# PCB-BI16-466.net
KiCad netlist of a schematic drawn in EAGLE
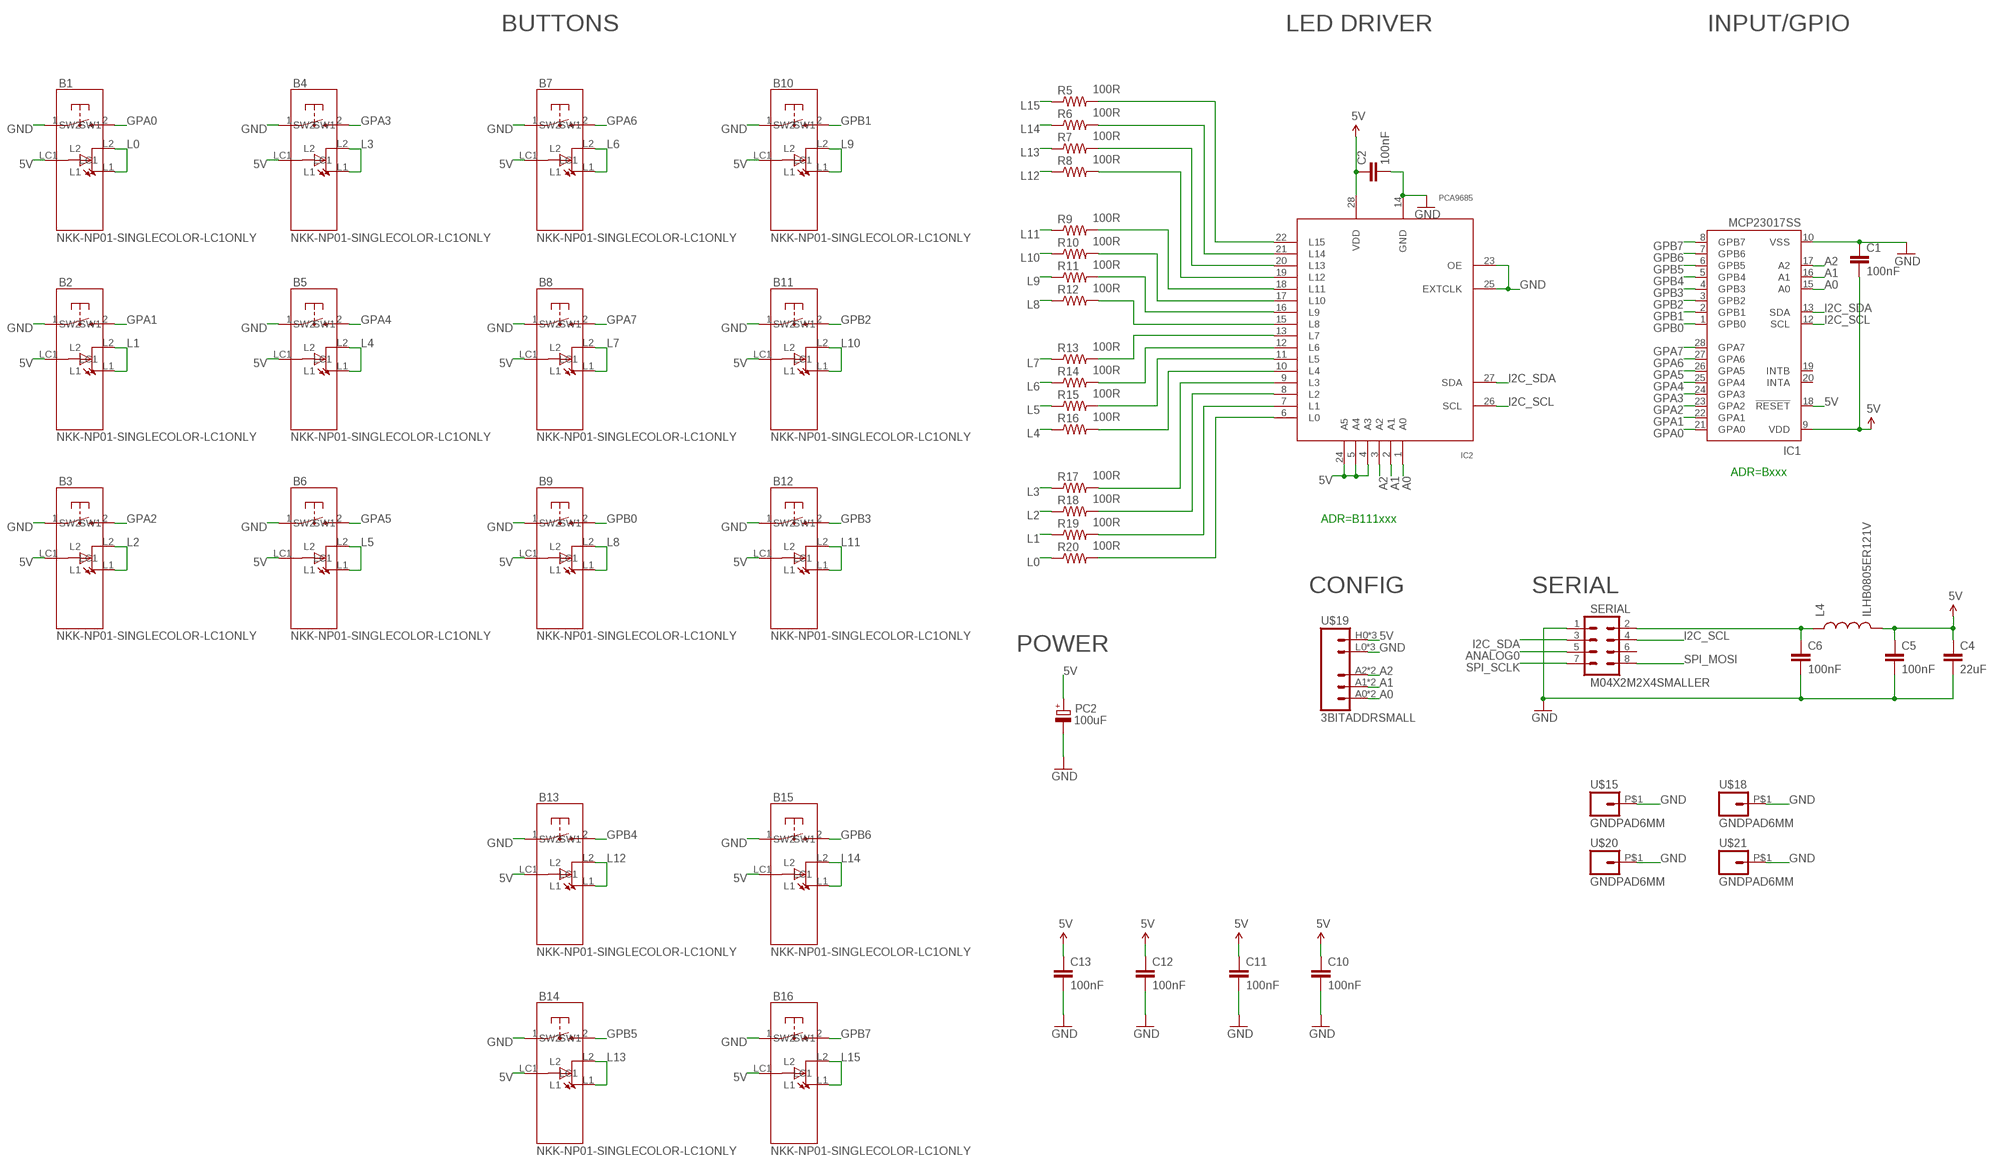
[diagram p0: schematic, sheet 1]

(export (version "E")
  (design (tool "Eeschema 10.0.6"))
  (components
    (comp (ref "B1")
      (value "NKK-NP01-SINGLECOLOR-LC1ONLY")
      (footprint "eagle-import:NKK-NP01_LESSHOLES2")
      (libsource (lib "eagle-import") (part "NKK-NP01-SINGLECOLOR-LC1ONLY"))
    )
    (comp (ref "B2")
      (value "NKK-NP01-SINGLECOLOR-LC1ONLY")
      (footprint "eagle-import:NKK-NP01_LESSHOLES2")
      (libsource (lib "eagle-import") (part "NKK-NP01-SINGLECOLOR-LC1ONLY"))
    )
    (comp (ref "B3")
      (value "NKK-NP01-SINGLECOLOR-LC1ONLY")
      (footprint "eagle-import:NKK-NP01_LESSHOLES2")
      (libsource (lib "eagle-import") (part "NKK-NP01-SINGLECOLOR-LC1ONLY"))
    )
    (comp (ref "B4")
      (value "NKK-NP01-SINGLECOLOR-LC1ONLY")
      (footprint "eagle-import:NKK-NP01_LESSHOLES2")
      (libsource (lib "eagle-import") (part "NKK-NP01-SINGLECOLOR-LC1ONLY"))
    )
    (comp (ref "B5")
      (value "NKK-NP01-SINGLECOLOR-LC1ONLY")
      (footprint "eagle-import:NKK-NP01_LESSHOLES2")
      (libsource (lib "eagle-import") (part "NKK-NP01-SINGLECOLOR-LC1ONLY"))
    )
    (comp (ref "B6")
      (value "NKK-NP01-SINGLECOLOR-LC1ONLY")
      (footprint "eagle-import:NKK-NP01_LESSHOLES2")
      (libsource (lib "eagle-import") (part "NKK-NP01-SINGLECOLOR-LC1ONLY"))
    )
    (comp (ref "B7")
      (value "NKK-NP01-SINGLECOLOR-LC1ONLY")
      (footprint "eagle-import:NKK-NP01_LESSHOLES2")
      (libsource (lib "eagle-import") (part "NKK-NP01-SINGLECOLOR-LC1ONLY"))
    )
    (comp (ref "B8")
      (value "NKK-NP01-SINGLECOLOR-LC1ONLY")
      (footprint "eagle-import:NKK-NP01_LESSHOLES2")
      (libsource (lib "eagle-import") (part "NKK-NP01-SINGLECOLOR-LC1ONLY"))
    )
    (comp (ref "B9")
      (value "NKK-NP01-SINGLECOLOR-LC1ONLY")
      (footprint "eagle-import:NKK-NP01_LESSHOLES2")
      (libsource (lib "eagle-import") (part "NKK-NP01-SINGLECOLOR-LC1ONLY"))
    )
    (comp (ref "B10")
      (value "NKK-NP01-SINGLECOLOR-LC1ONLY")
      (footprint "eagle-import:NKK-NP01_LESSHOLES2")
      (libsource (lib "eagle-import") (part "NKK-NP01-SINGLECOLOR-LC1ONLY"))
    )
    (comp (ref "B11")
      (value "NKK-NP01-SINGLECOLOR-LC1ONLY")
      (footprint "eagle-import:NKK-NP01_LESSHOLES2")
      (libsource (lib "eagle-import") (part "NKK-NP01-SINGLECOLOR-LC1ONLY"))
    )
    (comp (ref "B12")
      (value "NKK-NP01-SINGLECOLOR-LC1ONLY")
      (footprint "eagle-import:NKK-NP01_LESSHOLES2")
      (libsource (lib "eagle-import") (part "NKK-NP01-SINGLECOLOR-LC1ONLY"))
    )
    (comp (ref "B13")
      (value "NKK-NP01-SINGLECOLOR-LC1ONLY")
      (footprint "eagle-import:NKK-NP01_LESSHOLES2")
      (libsource (lib "eagle-import") (part "NKK-NP01-SINGLECOLOR-LC1ONLY"))
    )
    (comp (ref "B14")
      (value "NKK-NP01-SINGLECOLOR-LC1ONLY")
      (footprint "eagle-import:NKK-NP01_LESSHOLES2")
      (libsource (lib "eagle-import") (part "NKK-NP01-SINGLECOLOR-LC1ONLY"))
    )
    (comp (ref "B15")
      (value "NKK-NP01-SINGLECOLOR-LC1ONLY")
      (footprint "eagle-import:NKK-NP01_LESSHOLES2")
      (libsource (lib "eagle-import") (part "NKK-NP01-SINGLECOLOR-LC1ONLY"))
    )
    (comp (ref "B16")
      (value "NKK-NP01-SINGLECOLOR-LC1ONLY")
      (footprint "eagle-import:NKK-NP01_LESSHOLES2")
      (libsource (lib "eagle-import") (part "NKK-NP01-SINGLECOLOR-LC1ONLY"))
    )
    (comp (ref "C1")
      (value "100nF")
      (footprint "eagle-import:0603-CAP")
      (libsource (lib "eagle-import") (part "CAP0603-CAP"))
    )
    (comp (ref "C2")
      (value "100nF")
      (footprint "eagle-import:0603-CAP")
      (libsource (lib "eagle-import") (part "CAP0603-CAP"))
    )
    (comp (ref "C4")
      (value "22uF")
      (footprint "eagle-import:0805")
      (libsource (lib "eagle-import") (part "CAP0805"))
    )
    (comp (ref "C5")
      (value "100nF")
      (footprint "eagle-import:0603-CAP")
      (libsource (lib "eagle-import") (part "CAP0603-CAP"))
    )
    (comp (ref "C6")
      (value "100nF")
      (footprint "eagle-import:0603-CAP")
      (libsource (lib "eagle-import") (part "CAP0603-CAP"))
    )
    (comp (ref "C10")
      (value "100nF")
      (footprint "eagle-import:0603-CAP")
      (libsource (lib "eagle-import") (part "CAP0603-CAP"))
    )
    (comp (ref "C11")
      (value "100nF")
      (footprint "eagle-import:0603-CAP")
      (libsource (lib "eagle-import") (part "CAP0603-CAP"))
    )
    (comp (ref "C12")
      (value "100nF")
      (footprint "eagle-import:0603-CAP")
      (libsource (lib "eagle-import") (part "CAP0603-CAP"))
    )
    (comp (ref "C13")
      (value "100nF")
      (footprint "eagle-import:0603-CAP")
      (libsource (lib "eagle-import") (part "CAP0603-CAP"))
    )
    (comp (ref "IC1")
      (value "MCP23017SS")
      (footprint "eagle-import:SSOP28")
      (fields
        (field (name "MF") "MICROCHIP")
        (field (name "MPN") "MCP23017-E/SS")
        (field (name "MPN_1") "MCP23017-E/SS")
        (field (name "OC_FARNELL") "1467674")
        (field (name "OC_NEWARK") "31K2960")
      )
      (libsource (lib "eagle-import") (part "MCP23017SS"))
    )
    (comp (ref "IC2")
      (value "PCA9685")
      (footprint "eagle-import:TSSOP28")
      (libsource (lib "eagle-import") (part "PCA9685"))
    )
    (comp (ref "L4")
      (value "ILHB0805ER121V")
      (footprint "eagle-import:0805")
      (libsource (lib "eagle-import") (part "INDUCTOR0805"))
    )
    (comp (ref "PC2")
      (value "100uF")
      (footprint "eagle-import:PANASONIC_D")
      (libsource (lib "eagle-import") (part "CPOL-EUD"))
    )
    (comp (ref "R5")
      (value "100R")
      (footprint "eagle-import:0603-RES")
      (libsource (lib "eagle-import") (part "RESISTOR0603-RES"))
    )
    (comp (ref "R6")
      (value "100R")
      (footprint "eagle-import:0603-RES")
      (libsource (lib "eagle-import") (part "RESISTOR0603-RES"))
    )
    (comp (ref "R7")
      (value "100R")
      (footprint "eagle-import:0603-RES")
      (libsource (lib "eagle-import") (part "RESISTOR0603-RES"))
    )
    (comp (ref "R8")
      (value "100R")
      (footprint "eagle-import:0603-RES")
      (libsource (lib "eagle-import") (part "RESISTOR0603-RES"))
    )
    (comp (ref "R9")
      (value "100R")
      (footprint "eagle-import:0603-RES")
      (libsource (lib "eagle-import") (part "RESISTOR0603-RES"))
    )
    (comp (ref "R10")
      (value "100R")
      (footprint "eagle-import:0603-RES")
      (libsource (lib "eagle-import") (part "RESISTOR0603-RES"))
    )
    (comp (ref "R11")
      (value "100R")
      (footprint "eagle-import:0603-RES")
      (libsource (lib "eagle-import") (part "RESISTOR0603-RES"))
    )
    (comp (ref "R12")
      (value "100R")
      (footprint "eagle-import:0603-RES")
      (libsource (lib "eagle-import") (part "RESISTOR0603-RES"))
    )
    (comp (ref "R13")
      (value "100R")
      (footprint "eagle-import:0603-RES")
      (libsource (lib "eagle-import") (part "RESISTOR0603-RES"))
    )
    (comp (ref "R14")
      (value "100R")
      (footprint "eagle-import:0603-RES")
      (libsource (lib "eagle-import") (part "RESISTOR0603-RES"))
    )
    (comp (ref "R15")
      (value "100R")
      (footprint "eagle-import:0603-RES")
      (libsource (lib "eagle-import") (part "RESISTOR0603-RES"))
    )
    (comp (ref "R16")
      (value "100R")
      (footprint "eagle-import:0603-RES")
      (libsource (lib "eagle-import") (part "RESISTOR0603-RES"))
    )
    (comp (ref "R17")
      (value "100R")
      (footprint "eagle-import:0603-RES")
      (libsource (lib "eagle-import") (part "RESISTOR0603-RES"))
    )
    (comp (ref "R18")
      (value "100R")
      (footprint "eagle-import:0603-RES")
      (libsource (lib "eagle-import") (part "RESISTOR0603-RES"))
    )
    (comp (ref "R19")
      (value "100R")
      (footprint "eagle-import:0603-RES")
      (libsource (lib "eagle-import") (part "RESISTOR0603-RES"))
    )
    (comp (ref "R20")
      (value "100R")
      (footprint "eagle-import:0603-RES")
      (libsource (lib "eagle-import") (part "RESISTOR0603-RES"))
    )
    (comp (ref "SERIAL")
      (value "M04X2M2X4SMALLER")
      (footprint "eagle-import:M2X4SMALLER")
      (libsource (lib "eagle-import") (part "M04X2M2X4SMALLER"))
    )
    (comp (ref "U$15")
      (value "GNDPAD6MM")
      (footprint "eagle-import:3.2MMPAD6MM")
      (libsource (lib "eagle-import") (part "GNDPAD6MM"))
    )
    (comp (ref "U$18")
      (value "GNDPAD6MM")
      (footprint "eagle-import:3.2MMPAD6MM")
      (libsource (lib "eagle-import") (part "GNDPAD6MM"))
    )
    (comp (ref "U$19")
      (value "3BITADDRSMALL")
      (footprint "eagle-import:3BITADDR_SMALL")
      (libsource (lib "eagle-import") (part "3BITADDRSMALL"))
    )
    (comp (ref "U$20")
      (value "GNDPAD6MM")
      (footprint "eagle-import:3.2MMPAD6MM")
      (libsource (lib "eagle-import") (part "GNDPAD6MM"))
    )
    (comp (ref "U$21")
      (value "GNDPAD6MM")
      (footprint "eagle-import:3.2MMPAD6MM")
      (libsource (lib "eagle-import") (part "GNDPAD6MM"))
    )
  )
  (nets
    (net (code "1") (name "5V") (class "Default")
      (node (ref "B1") (pin "LC1") (pinfunction "LC1_LC1") (pintype "bidirectional"))
      (node (ref "B10") (pin "LC1") (pinfunction "LC1_LC1") (pintype "bidirectional"))
      (node (ref "B11") (pin "LC1") (pinfunction "LC1_LC1") (pintype "bidirectional"))
      (node (ref "B12") (pin "LC1") (pinfunction "LC1_LC1") (pintype "bidirectional"))
      (node (ref "B13") (pin "LC1") (pinfunction "LC1_LC1") (pintype "bidirectional"))
      (node (ref "B14") (pin "LC1") (pinfunction "LC1_LC1") (pintype "bidirectional"))
      (node (ref "B15") (pin "LC1") (pinfunction "LC1_LC1") (pintype "bidirectional"))
      (node (ref "B16") (pin "LC1") (pinfunction "LC1_LC1") (pintype "bidirectional"))
      (node (ref "B2") (pin "LC1") (pinfunction "LC1_LC1") (pintype "bidirectional"))
      (node (ref "B3") (pin "LC1") (pinfunction "LC1_LC1") (pintype "bidirectional"))
      (node (ref "B4") (pin "LC1") (pinfunction "LC1_LC1") (pintype "bidirectional"))
      (node (ref "B5") (pin "LC1") (pinfunction "LC1_LC1") (pintype "bidirectional"))
      (node (ref "B6") (pin "LC1") (pinfunction "LC1_LC1") (pintype "bidirectional"))
      (node (ref "B7") (pin "LC1") (pinfunction "LC1_LC1") (pintype "bidirectional"))
      (node (ref "B8") (pin "LC1") (pinfunction "LC1_LC1") (pintype "bidirectional"))
      (node (ref "B9") (pin "LC1") (pinfunction "LC1_LC1") (pintype "bidirectional"))
      (node (ref "C1") (pin "2") (pinfunction "2_2") (pintype "passive"))
      (node (ref "C10") (pin "1") (pinfunction "1_1") (pintype "passive"))
      (node (ref "C11") (pin "1") (pinfunction "1_1") (pintype "passive"))
      (node (ref "C12") (pin "1") (pinfunction "1_1") (pintype "passive"))
      (node (ref "C13") (pin "1") (pinfunction "1_1") (pintype "passive"))
      (node (ref "C2") (pin "1") (pinfunction "1_1") (pintype "passive"))
      (node (ref "C4") (pin "1") (pinfunction "1_1") (pintype "passive"))
      (node (ref "C5") (pin "1") (pinfunction "1_1") (pintype "passive"))
      (node (ref "IC1") (pin "18") (pinfunction "~{RESET}_18") (pintype "input"))
      (node (ref "IC1") (pin "9") (pinfunction "VDD_9") (pintype "power_in"))
      (node (ref "IC2") (pin "24") (pinfunction "A5_24") (pintype "input"))
      (node (ref "IC2") (pin "28") (pinfunction "VDD_28") (pintype "power_in"))
      (node (ref "IC2") (pin "4") (pinfunction "A3_4") (pintype "input"))
      (node (ref "IC2") (pin "5") (pinfunction "A4_5") (pintype "input"))
      (node (ref "L4") (pin "2") (pinfunction "2_2") (pintype "passive"))
      (node (ref "PC2") (pin "+") (pinfunction "+_+") (pintype "passive"))
      (node (ref "U$19") (pin "H0") (pinfunction "VCC_H0") (pintype "passive"))
      (node (ref "U$19") (pin "H1") (pinfunction "VCC_H1") (pintype "passive"))
      (node (ref "U$19") (pin "H2") (pinfunction "VCC_H2") (pintype "passive"))
    )
    (net (code "2") (name "A0") (class "Default")
      (node (ref "IC1") (pin "15") (pinfunction "A0_15") (pintype "input"))
      (node (ref "IC2") (pin "1") (pinfunction "A0_1") (pintype "input"))
      (node (ref "U$19") (pin "A0") (pinfunction "A0_A0") (pintype "passive"))
      (node (ref "U$19") (pin "AS0") (pinfunction "A0_AS0") (pintype "passive"))
    )
    (net (code "3") (name "A1") (class "Default")
      (node (ref "IC1") (pin "16") (pinfunction "A1_16") (pintype "input"))
      (node (ref "IC2") (pin "2") (pinfunction "A1_2") (pintype "input"))
      (node (ref "U$19") (pin "A1") (pinfunction "A1_A1") (pintype "passive"))
      (node (ref "U$19") (pin "AS1") (pinfunction "A1_AS1") (pintype "passive"))
    )
    (net (code "4") (name "A2") (class "Default")
      (node (ref "IC1") (pin "17") (pinfunction "A2_17") (pintype "input"))
      (node (ref "IC2") (pin "3") (pinfunction "A2_3") (pintype "input"))
      (node (ref "U$19") (pin "A2") (pinfunction "A2_A2") (pintype "passive"))
      (node (ref "U$19") (pin "AS2") (pinfunction "A2_AS2") (pintype "passive"))
    )
    (net (code "5") (name "ANALOG0") (class "Default")
      (node (ref "SERIAL") (pin "5") (pinfunction "5_5") (pintype "passive"))
    )
    (net (code "6") (name "GND") (class "Default")
      (node (ref "B1") (pin "1") (pinfunction "SW1_1") (pintype "bidirectional"))
      (node (ref "B10") (pin "1") (pinfunction "SW1_1") (pintype "bidirectional"))
      (node (ref "B11") (pin "1") (pinfunction "SW1_1") (pintype "bidirectional"))
      (node (ref "B12") (pin "1") (pinfunction "SW1_1") (pintype "bidirectional"))
      (node (ref "B13") (pin "1") (pinfunction "SW1_1") (pintype "bidirectional"))
      (node (ref "B14") (pin "1") (pinfunction "SW1_1") (pintype "bidirectional"))
      (node (ref "B15") (pin "1") (pinfunction "SW1_1") (pintype "bidirectional"))
      (node (ref "B16") (pin "1") (pinfunction "SW1_1") (pintype "bidirectional"))
      (node (ref "B2") (pin "1") (pinfunction "SW1_1") (pintype "bidirectional"))
      (node (ref "B3") (pin "1") (pinfunction "SW1_1") (pintype "bidirectional"))
      (node (ref "B4") (pin "1") (pinfunction "SW1_1") (pintype "bidirectional"))
      (node (ref "B5") (pin "1") (pinfunction "SW1_1") (pintype "bidirectional"))
      (node (ref "B6") (pin "1") (pinfunction "SW1_1") (pintype "bidirectional"))
      (node (ref "B7") (pin "1") (pinfunction "SW1_1") (pintype "bidirectional"))
      (node (ref "B8") (pin "1") (pinfunction "SW1_1") (pintype "bidirectional"))
      (node (ref "B9") (pin "1") (pinfunction "SW1_1") (pintype "bidirectional"))
      (node (ref "C1") (pin "1") (pinfunction "1_1") (pintype "passive"))
      (node (ref "C10") (pin "2") (pinfunction "2_2") (pintype "passive"))
      (node (ref "C11") (pin "2") (pinfunction "2_2") (pintype "passive"))
      (node (ref "C12") (pin "2") (pinfunction "2_2") (pintype "passive"))
      (node (ref "C13") (pin "2") (pinfunction "2_2") (pintype "passive"))
      (node (ref "C2") (pin "2") (pinfunction "2_2") (pintype "passive"))
      (node (ref "C4") (pin "2") (pinfunction "2_2") (pintype "passive"))
      (node (ref "C5") (pin "2") (pinfunction "2_2") (pintype "passive"))
      (node (ref "C6") (pin "2") (pinfunction "2_2") (pintype "passive"))
      (node (ref "IC1") (pin "10") (pinfunction "VSS_10") (pintype "power_in"))
      (node (ref "IC2") (pin "14") (pinfunction "GND_14") (pintype "power_in"))
      (node (ref "IC2") (pin "23") (pinfunction "OE_23") (pintype "input"))
      (node (ref "IC2") (pin "25") (pinfunction "EXTCLK_25") (pintype "input"))
      (node (ref "PC2") (pin "-") (pinfunction "-_-") (pintype "passive"))
      (node (ref "SERIAL") (pin "1") (pinfunction "1_1") (pintype "passive"))
      (node (ref "U$15") (pin "P$1") (pinfunction "1_P$1") (pintype "passive"))
      (node (ref "U$18") (pin "P$1") (pinfunction "1_P$1") (pintype "passive"))
      (node (ref "U$19") (pin "L0") (pinfunction "GND_L0") (pintype "passive"))
      (node (ref "U$19") (pin "L1") (pinfunction "GND_L1") (pintype "passive"))
      (node (ref "U$19") (pin "L2") (pinfunction "GND_L2") (pintype "passive"))
      (node (ref "U$20") (pin "P$1") (pinfunction "1_P$1") (pintype "passive"))
      (node (ref "U$21") (pin "P$1") (pinfunction "1_P$1") (pintype "passive"))
    )
    (net (code "7") (name "GPA0") (class "Default")
      (node (ref "B1") (pin "2") (pinfunction "SW2_2") (pintype "bidirectional"))
      (node (ref "IC1") (pin "21") (pinfunction "GPA0_21") (pintype "bidirectional"))
    )
    (net (code "8") (name "GPA1") (class "Default")
      (node (ref "B2") (pin "2") (pinfunction "SW2_2") (pintype "bidirectional"))
      (node (ref "IC1") (pin "22") (pinfunction "GPA1_22") (pintype "bidirectional"))
    )
    (net (code "9") (name "GPA2") (class "Default")
      (node (ref "B3") (pin "2") (pinfunction "SW2_2") (pintype "bidirectional"))
      (node (ref "IC1") (pin "23") (pinfunction "GPA2_23") (pintype "bidirectional"))
    )
    (net (code "10") (name "GPA3") (class "Default")
      (node (ref "B4") (pin "2") (pinfunction "SW2_2") (pintype "bidirectional"))
      (node (ref "IC1") (pin "24") (pinfunction "GPA3_24") (pintype "bidirectional"))
    )
    (net (code "11") (name "GPA4") (class "Default")
      (node (ref "B5") (pin "2") (pinfunction "SW2_2") (pintype "bidirectional"))
      (node (ref "IC1") (pin "25") (pinfunction "GPA4_25") (pintype "bidirectional"))
    )
    (net (code "12") (name "GPA5") (class "Default")
      (node (ref "B6") (pin "2") (pinfunction "SW2_2") (pintype "bidirectional"))
      (node (ref "IC1") (pin "26") (pinfunction "GPA5_26") (pintype "bidirectional"))
    )
    (net (code "13") (name "GPA6") (class "Default")
      (node (ref "B7") (pin "2") (pinfunction "SW2_2") (pintype "bidirectional"))
      (node (ref "IC1") (pin "27") (pinfunction "GPA6_27") (pintype "bidirectional"))
    )
    (net (code "14") (name "GPA7") (class "Default")
      (node (ref "B8") (pin "2") (pinfunction "SW2_2") (pintype "bidirectional"))
      (node (ref "IC1") (pin "28") (pinfunction "GPA7_28") (pintype "bidirectional"))
    )
    (net (code "15") (name "GPB0") (class "Default")
      (node (ref "B9") (pin "2") (pinfunction "SW2_2") (pintype "bidirectional"))
      (node (ref "IC1") (pin "1") (pinfunction "GPB0_1") (pintype "bidirectional"))
    )
    (net (code "16") (name "GPB1") (class "Default")
      (node (ref "B10") (pin "2") (pinfunction "SW2_2") (pintype "bidirectional"))
      (node (ref "IC1") (pin "2") (pinfunction "GPB1_2") (pintype "bidirectional"))
    )
    (net (code "17") (name "GPB2") (class "Default")
      (node (ref "B11") (pin "2") (pinfunction "SW2_2") (pintype "bidirectional"))
      (node (ref "IC1") (pin "3") (pinfunction "GPB2_3") (pintype "bidirectional"))
    )
    (net (code "18") (name "GPB3") (class "Default")
      (node (ref "B12") (pin "2") (pinfunction "SW2_2") (pintype "bidirectional"))
      (node (ref "IC1") (pin "4") (pinfunction "GPB3_4") (pintype "bidirectional"))
    )
    (net (code "19") (name "GPB4") (class "Default")
      (node (ref "B13") (pin "2") (pinfunction "SW2_2") (pintype "bidirectional"))
      (node (ref "IC1") (pin "5") (pinfunction "GPB4_5") (pintype "bidirectional"))
    )
    (net (code "20") (name "GPB5") (class "Default")
      (node (ref "B14") (pin "2") (pinfunction "SW2_2") (pintype "bidirectional"))
      (node (ref "IC1") (pin "6") (pinfunction "GPB5_6") (pintype "bidirectional"))
    )
    (net (code "21") (name "GPB6") (class "Default")
      (node (ref "B15") (pin "2") (pinfunction "SW2_2") (pintype "bidirectional"))
      (node (ref "IC1") (pin "7") (pinfunction "GPB6_7") (pintype "bidirectional"))
    )
    (net (code "22") (name "GPB7") (class "Default")
      (node (ref "B16") (pin "2") (pinfunction "SW2_2") (pintype "bidirectional"))
      (node (ref "IC1") (pin "8") (pinfunction "GPB7_8") (pintype "bidirectional"))
    )
    (net (code "23") (name "I2C_SCL") (class "Default")
      (node (ref "IC1") (pin "12") (pinfunction "SCL_12") (pintype "input"))
      (node (ref "IC2") (pin "26") (pinfunction "SCL_26") (pintype "input"))
      (node (ref "SERIAL") (pin "4") (pinfunction "4_4") (pintype "passive"))
    )
    (net (code "24") (name "I2C_SDA") (class "Default")
      (node (ref "IC1") (pin "13") (pinfunction "SDA_13") (pintype "bidirectional"))
      (node (ref "IC2") (pin "27") (pinfunction "SDA_27") (pintype "input"))
      (node (ref "SERIAL") (pin "3") (pinfunction "3_3") (pintype "passive"))
    )
    (net (code "25") (name "L0") (class "Default")
      (node (ref "B1") (pin "L1") (pinfunction "L1_L1") (pintype "bidirectional"))
      (node (ref "B1") (pin "L2") (pinfunction "L2_L2") (pintype "bidirectional"))
      (node (ref "R20") (pin "1") (pinfunction "1_1") (pintype "passive"))
    )
    (net (code "26") (name "L1") (class "Default")
      (node (ref "B2") (pin "L1") (pinfunction "L1_L1") (pintype "bidirectional"))
      (node (ref "B2") (pin "L2") (pinfunction "L2_L2") (pintype "bidirectional"))
      (node (ref "R19") (pin "1") (pinfunction "1_1") (pintype "passive"))
    )
    (net (code "27") (name "L2") (class "Default")
      (node (ref "B3") (pin "L1") (pinfunction "L1_L1") (pintype "bidirectional"))
      (node (ref "B3") (pin "L2") (pinfunction "L2_L2") (pintype "bidirectional"))
      (node (ref "R18") (pin "1") (pinfunction "1_1") (pintype "passive"))
    )
    (net (code "28") (name "L3") (class "Default")
      (node (ref "B4") (pin "L1") (pinfunction "L1_L1") (pintype "bidirectional"))
      (node (ref "B4") (pin "L2") (pinfunction "L2_L2") (pintype "bidirectional"))
      (node (ref "R17") (pin "1") (pinfunction "1_1") (pintype "passive"))
    )
    (net (code "29") (name "L4") (class "Default")
      (node (ref "B5") (pin "L1") (pinfunction "L1_L1") (pintype "bidirectional"))
      (node (ref "B5") (pin "L2") (pinfunction "L2_L2") (pintype "bidirectional"))
      (node (ref "R16") (pin "1") (pinfunction "1_1") (pintype "passive"))
    )
    (net (code "30") (name "L5") (class "Default")
      (node (ref "B6") (pin "L1") (pinfunction "L1_L1") (pintype "bidirectional"))
      (node (ref "B6") (pin "L2") (pinfunction "L2_L2") (pintype "bidirectional"))
      (node (ref "R15") (pin "1") (pinfunction "1_1") (pintype "passive"))
    )
    (net (code "31") (name "L6") (class "Default")
      (node (ref "B7") (pin "L1") (pinfunction "L1_L1") (pintype "bidirectional"))
      (node (ref "B7") (pin "L2") (pinfunction "L2_L2") (pintype "bidirectional"))
      (node (ref "R14") (pin "1") (pinfunction "1_1") (pintype "passive"))
    )
    (net (code "32") (name "L7") (class "Default")
      (node (ref "B8") (pin "L1") (pinfunction "L1_L1") (pintype "bidirectional"))
      (node (ref "B8") (pin "L2") (pinfunction "L2_L2") (pintype "bidirectional"))
      (node (ref "R13") (pin "1") (pinfunction "1_1") (pintype "passive"))
    )
    (net (code "33") (name "L8") (class "Default")
      (node (ref "B9") (pin "L1") (pinfunction "L1_L1") (pintype "bidirectional"))
      (node (ref "B9") (pin "L2") (pinfunction "L2_L2") (pintype "bidirectional"))
      (node (ref "R12") (pin "1") (pinfunction "1_1") (pintype "passive"))
    )
    (net (code "34") (name "L9") (class "Default")
      (node (ref "B10") (pin "L1") (pinfunction "L1_L1") (pintype "bidirectional"))
      (node (ref "B10") (pin "L2") (pinfunction "L2_L2") (pintype "bidirectional"))
      (node (ref "R11") (pin "1") (pinfunction "1_1") (pintype "passive"))
    )
    (net (code "35") (name "L10") (class "Default")
      (node (ref "B11") (pin "L1") (pinfunction "L1_L1") (pintype "bidirectional"))
      (node (ref "B11") (pin "L2") (pinfunction "L2_L2") (pintype "bidirectional"))
      (node (ref "R10") (pin "1") (pinfunction "1_1") (pintype "passive"))
    )
    (net (code "36") (name "L11") (class "Default")
      (node (ref "B12") (pin "L1") (pinfunction "L1_L1") (pintype "bidirectional"))
      (node (ref "B12") (pin "L2") (pinfunction "L2_L2") (pintype "bidirectional"))
      (node (ref "R9") (pin "1") (pinfunction "1_1") (pintype "passive"))
    )
    (net (code "37") (name "L12") (class "Default")
      (node (ref "B13") (pin "L1") (pinfunction "L1_L1") (pintype "bidirectional"))
      (node (ref "B13") (pin "L2") (pinfunction "L2_L2") (pintype "bidirectional"))
      (node (ref "R8") (pin "1") (pinfunction "1_1") (pintype "passive"))
    )
    (net (code "38") (name "L13") (class "Default")
      (node (ref "B14") (pin "L1") (pinfunction "L1_L1") (pintype "bidirectional"))
      (node (ref "B14") (pin "L2") (pinfunction "L2_L2") (pintype "bidirectional"))
      (node (ref "R7") (pin "1") (pinfunction "1_1") (pintype "passive"))
    )
    (net (code "39") (name "L14") (class "Default")
      (node (ref "B15") (pin "L1") (pinfunction "L1_L1") (pintype "bidirectional"))
      (node (ref "B15") (pin "L2") (pinfunction "L2_L2") (pintype "bidirectional"))
      (node (ref "R6") (pin "1") (pinfunction "1_1") (pintype "passive"))
    )
    (net (code "40") (name "L15") (class "Default")
      (node (ref "B16") (pin "L1") (pinfunction "L1_L1") (pintype "bidirectional"))
      (node (ref "B16") (pin "L2") (pinfunction "L2_L2") (pintype "bidirectional"))
      (node (ref "R5") (pin "1") (pinfunction "1_1") (pintype "passive"))
    )
    (net (code "41") (name "Net-(C6-Pad1)") (class "Default")
      (node (ref "C6") (pin "1") (pinfunction "1_1") (pintype "passive"))
      (node (ref "L4") (pin "1") (pinfunction "1_1") (pintype "passive"))
      (node (ref "SERIAL") (pin "2") (pinfunction "2_2") (pintype "passive"))
    )
    (net (code "42") (name "Net-(IC2-L0)") (class "Default")
      (node (ref "IC2") (pin "6") (pinfunction "L0_6") (pintype "output"))
      (node (ref "R20") (pin "2") (pinfunction "2_2") (pintype "passive"))
    )
    (net (code "43") (name "Net-(IC2-L1)") (class "Default")
      (node (ref "IC2") (pin "7") (pinfunction "L1_7") (pintype "output"))
      (node (ref "R19") (pin "2") (pinfunction "2_2") (pintype "passive"))
    )
    (net (code "44") (name "Net-(IC2-L2)") (class "Default")
      (node (ref "IC2") (pin "8") (pinfunction "L2_8") (pintype "output"))
      (node (ref "R18") (pin "2") (pinfunction "2_2") (pintype "passive"))
    )
    (net (code "45") (name "Net-(IC2-L3)") (class "Default")
      (node (ref "IC2") (pin "9") (pinfunction "L3_9") (pintype "output"))
      (node (ref "R17") (pin "2") (pinfunction "2_2") (pintype "passive"))
    )
    (net (code "46") (name "Net-(IC2-L4)") (class "Default")
      (node (ref "IC2") (pin "10") (pinfunction "L4_10") (pintype "output"))
      (node (ref "R16") (pin "2") (pinfunction "2_2") (pintype "passive"))
    )
    (net (code "47") (name "Net-(IC2-L5)") (class "Default")
      (node (ref "IC2") (pin "11") (pinfunction "L5_11") (pintype "output"))
      (node (ref "R15") (pin "2") (pinfunction "2_2") (pintype "passive"))
    )
    (net (code "48") (name "Net-(IC2-L6)") (class "Default")
      (node (ref "IC2") (pin "12") (pinfunction "L6_12") (pintype "output"))
      (node (ref "R14") (pin "2") (pinfunction "2_2") (pintype "passive"))
    )
    (net (code "49") (name "Net-(IC2-L7)") (class "Default")
      (node (ref "IC2") (pin "13") (pinfunction "L7_13") (pintype "output"))
      (node (ref "R13") (pin "2") (pinfunction "2_2") (pintype "passive"))
    )
    (net (code "50") (name "Net-(IC2-L8)") (class "Default")
      (node (ref "IC2") (pin "15") (pinfunction "L8_15") (pintype "output"))
      (node (ref "R12") (pin "2") (pinfunction "2_2") (pintype "passive"))
    )
    (net (code "51") (name "Net-(IC2-L9)") (class "Default")
      (node (ref "IC2") (pin "16") (pinfunction "L9_16") (pintype "output"))
      (node (ref "R11") (pin "2") (pinfunction "2_2") (pintype "passive"))
    )
    (net (code "52") (name "Net-(IC2-L10)") (class "Default")
      (node (ref "IC2") (pin "17") (pinfunction "L10_17") (pintype "output"))
      (node (ref "R10") (pin "2") (pinfunction "2_2") (pintype "passive"))
    )
    (net (code "53") (name "Net-(IC2-L11)") (class "Default")
      (node (ref "IC2") (pin "18") (pinfunction "L11_18") (pintype "output"))
      (node (ref "R9") (pin "2") (pinfunction "2_2") (pintype "passive"))
    )
    (net (code "54") (name "Net-(IC2-L12)") (class "Default")
      (node (ref "IC2") (pin "19") (pinfunction "L12_19") (pintype "output"))
      (node (ref "R8") (pin "2") (pinfunction "2_2") (pintype "passive"))
    )
    (net (code "55") (name "Net-(IC2-L13)") (class "Default")
      (node (ref "IC2") (pin "20") (pinfunction "L13_20") (pintype "output"))
      (node (ref "R7") (pin "2") (pinfunction "2_2") (pintype "passive"))
    )
    (net (code "56") (name "Net-(IC2-L14)") (class "Default")
      (node (ref "IC2") (pin "21") (pinfunction "L14_21") (pintype "output"))
      (node (ref "R6") (pin "2") (pinfunction "2_2") (pintype "passive"))
    )
    (net (code "57") (name "Net-(IC2-L15)") (class "Default")
      (node (ref "IC2") (pin "22") (pinfunction "L15_22") (pintype "output"))
      (node (ref "R5") (pin "2") (pinfunction "2_2") (pintype "passive"))
    )
    (net (code "58") (name "SPI_MOSI") (class "Default")
      (node (ref "SERIAL") (pin "8") (pinfunction "8_8") (pintype "passive"))
    )
    (net (code "59") (name "SPI_SCLK") (class "Default")
      (node (ref "SERIAL") (pin "7") (pinfunction "7_7") (pintype "passive"))
    )
    (net (code "60") (name "unconnected-(IC1-INTA-Pad20)") (class "Default")
      (node (ref "IC1") (pin "20") (pinfunction "INTA_20") (pintype "output"))
    )
    (net (code "61") (name "unconnected-(IC1-INTB-Pad19)") (class "Default")
      (node (ref "IC1") (pin "19") (pinfunction "INTB_19") (pintype "output"))
    )
    (net (code "62") (name "unconnected-(SERIAL-Pad6)") (class "Default")
      (node (ref "SERIAL") (pin "6") (pinfunction "6_6") (pintype "passive"))
    )
  )
)
